# XRACER-IMU-R07.net
KiCad netlist of a schematic drawn in Altium Designer
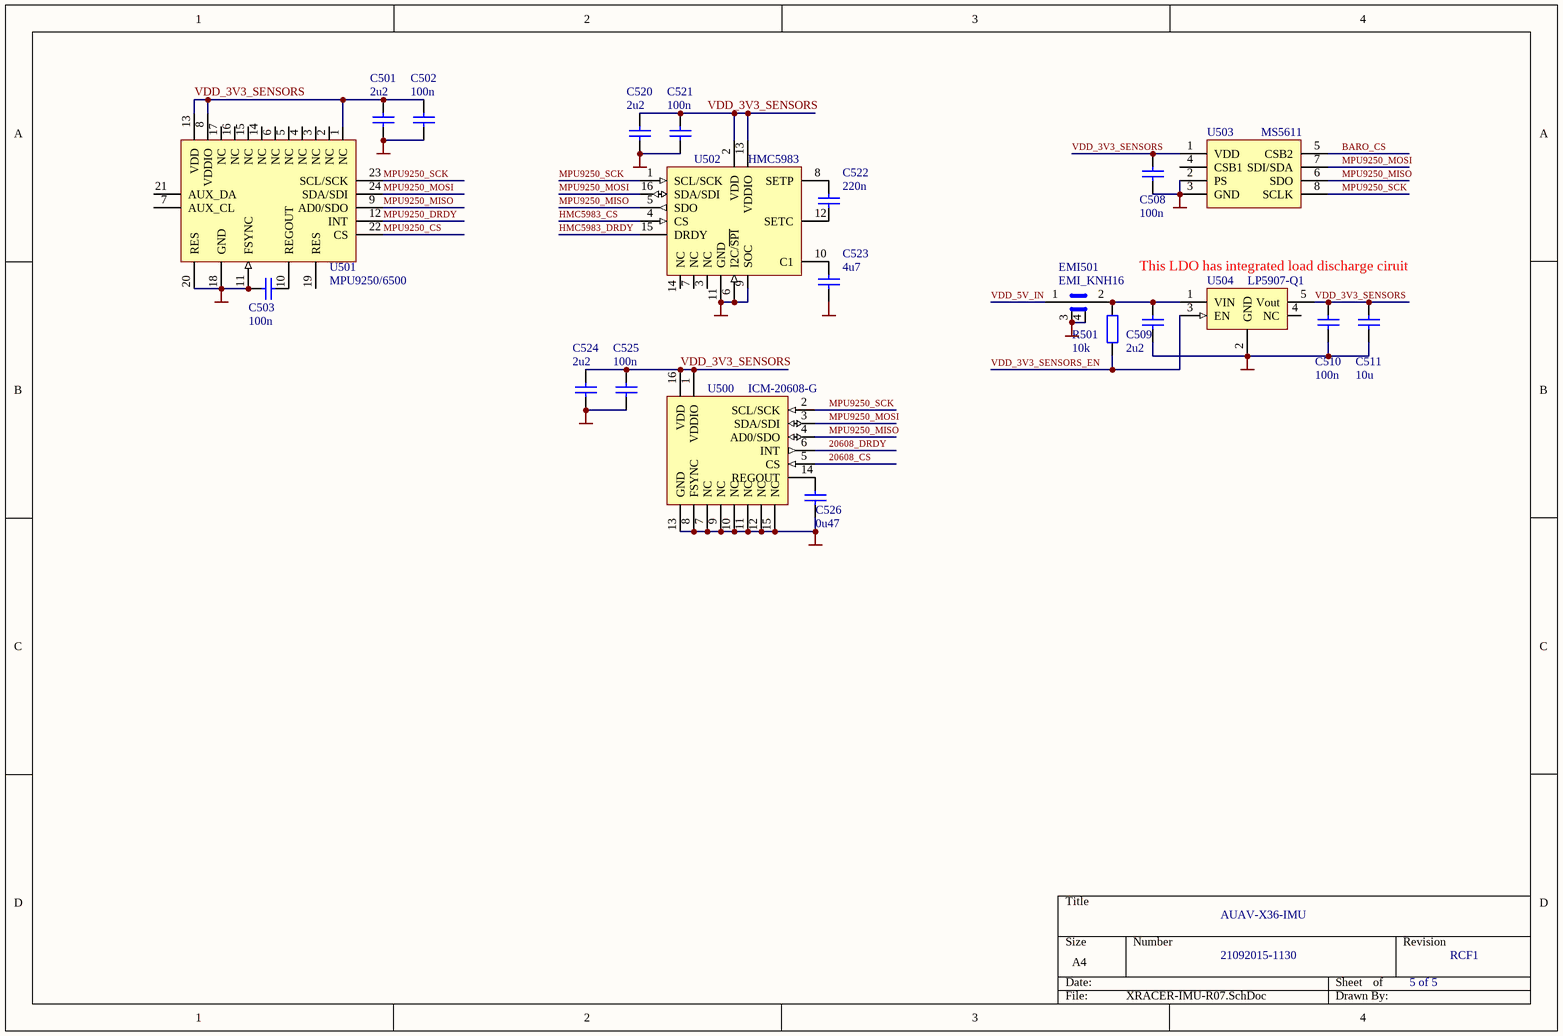
[diagram p0: XRACER-IMU-R07.SchDoc]

(export (version "E")
  (design (tool "Eeschema 10.0.6"))
  (components
    (comp (ref "C501")
      (value "2u2")
      (footprint "0402A")
      (description "Capacitor")
      (fields (field (name "PUBLISHER") "Altium Limited"))
      (libsource (lib "Miscellaneous Devices") (part "Cap"))
    )
    (comp (ref "C502")
      (value "100n")
      (footprint "0402A")
      (description "Capacitor")
      (fields (field (name "PUBLISHER") "Altium Limited"))
      (libsource (lib "Miscellaneous Devices") (part "Cap"))
    )
    (comp (ref "C503")
      (value "100n")
      (footprint "0402A")
      (description "Capacitor")
      (fields (field (name "PUBLISHER") "Altium Limited"))
      (libsource (lib "Miscellaneous Devices") (part "Cap"))
    )
    (comp (ref "C508")
      (value "100n")
      (footprint "0402A")
      (description "Capacitor")
      (fields (field (name "PUBLISHER") "Altium Limited"))
      (libsource (lib "Miscellaneous Devices") (part "Cap"))
    )
    (comp (ref "C509")
      (value "2u2")
      (footprint "0603A")
      (description "Capacitor")
      (fields (field (name "PUBLISHER") "Altium Limited"))
      (libsource (lib "Miscellaneous Devices") (part "Cap"))
    )
    (comp (ref "C510")
      (value "100n")
      (footprint "0603A")
      (description "Capacitor")
      (fields (field (name "PUBLISHER") "Altium Limited"))
      (libsource (lib "Miscellaneous Devices") (part "Cap"))
    )
    (comp (ref "C511")
      (value "10u")
      (footprint "0603A")
      (description "Capacitor")
      (fields (field (name "PUBLISHER") "Altium Limited"))
      (libsource (lib "Miscellaneous Devices") (part "Cap"))
    )
    (comp (ref "C520")
      (value "2u2")
      (footprint "0402A")
      (description "Capacitor")
      (fields (field (name "PUBLISHER") "Altium Limited"))
      (libsource (lib "Miscellaneous Devices") (part "Cap"))
    )
    (comp (ref "C521")
      (value "100n")
      (footprint "0402A")
      (description "Capacitor")
      (fields (field (name "PUBLISHER") "Altium Limited"))
      (libsource (lib "Miscellaneous Devices") (part "Cap"))
    )
    (comp (ref "C522")
      (value "220n")
      (footprint "0402A")
      (description "Capacitor")
      (fields (field (name "PUBLISHER") "Altium Limited"))
      (libsource (lib "Miscellaneous Devices") (part "Cap"))
    )
    (comp (ref "C523")
      (value "4u7")
      (footprint "0603A")
      (description "Capacitor")
      (fields (field (name "PUBLISHER") "Altium Limited"))
      (libsource (lib "Miscellaneous Devices") (part "Cap"))
    )
    (comp (ref "C524")
      (value "2u2")
      (footprint "0402A")
      (description "Capacitor")
      (fields (field (name "PUBLISHER") "Altium Limited"))
      (libsource (lib "Miscellaneous Devices") (part "Cap"))
    )
    (comp (ref "C525")
      (value "100n")
      (footprint "0402A")
      (description "Capacitor")
      (fields (field (name "PUBLISHER") "Altium Limited"))
      (libsource (lib "Miscellaneous Devices") (part "Cap"))
    )
    (comp (ref "C526")
      (value "0u47")
      (footprint "0402A")
      (description "Capacitor")
      (fields (field (name "PUBLISHER") "Altium Limited"))
      (libsource (lib "Miscellaneous Devices") (part "Cap"))
    )
    (comp (ref "EMI501")
      (value "EMI_KNH16")
      (footprint "EMI_KNH16_0603")
      (libsource (lib "My_Altium") (part "EMI_KNH16"))
    )
    (comp (ref "R501")
      (value "10k")
      (footprint "0603A")
      (description "Resistor")
      (fields (field (name "PUBLISHER") "Altium Limited"))
      (libsource (lib "Miscellaneous Devices") (part "Res2"))
    )
    (comp (ref "U500")
      (value "ICM-20608-G")
      (footprint "HCLGA-16L")
      (libsource (lib "My_Altium") (part "ICM-20608-G"))
    )
    (comp (ref "U501")
      (value "MPU9250/6500")
      (footprint "MPU6500-9250")
      (libsource (lib "My_Altium") (part "MPU6500"))
    )
    (comp (ref "U502")
      (value "HMC5983")
      (footprint "HMC5883L")
      (libsource (lib "My_Altium") (part "HMC5983"))
    )
    (comp (ref "U503")
      (value "MS5611")
      (footprint "MS5611")
      (libsource (lib "My_Altium") (part "MS5611-01BA03"))
    )
    (comp (ref "U504")
      (value "LP5907-Q1")
      (footprint "SOT23-5")
      (libsource (lib "My_Altium") (part "LP5907-Q1"))
    )
  )
  (nets
    (net (code "1") (name "/20608_CS") (class "Default")
      (node (ref "U500") (pin "5") (pinfunction "CS_5") (pintype "input"))
    )
    (net (code "2") (name "/20608_DRDY") (class "Default")
      (node (ref "U500") (pin "6") (pinfunction "INT_6") (pintype "output"))
    )
    (net (code "3") (name "/BARO_CS") (class "Default")
      (node (ref "U503") (pin "5") (pinfunction "CSB2_5") (pintype "passive"))
    )
    (net (code "4") (name "/HMC5983_CS") (class "Default")
      (node (ref "U502") (pin "4") (pinfunction "CS_4") (pintype "input"))
    )
    (net (code "5") (name "/HMC5983_DRDY") (class "Default")
      (node (ref "U502") (pin "15") (pinfunction "DRDY_15") (pintype "passive"))
    )
    (net (code "6") (name "/MPU9250_CS") (class "Default")
      (node (ref "U501") (pin "22") (pinfunction "CS_22") (pintype "passive"))
    )
    (net (code "7") (name "/MPU9250_DRDY") (class "Default")
      (node (ref "U501") (pin "12") (pinfunction "INT_12") (pintype "passive"))
    )
    (net (code "8") (name "/MPU9250_MISO") (class "Default")
      (node (ref "U500") (pin "4") (pinfunction "AD0/SDO_4") (pintype "bidirectional"))
      (node (ref "U501") (pin "9") (pinfunction "AD0/SDO_9") (pintype "passive"))
      (node (ref "U502") (pin "5") (pinfunction "SDO_5") (pintype "output"))
      (node (ref "U503") (pin "6") (pinfunction "SDO_6") (pintype "passive"))
    )
    (net (code "9") (name "/MPU9250_MOSI") (class "Default")
      (node (ref "U500") (pin "3") (pinfunction "SDA/SDI_3") (pintype "bidirectional"))
      (node (ref "U501") (pin "24") (pinfunction "SDA/SDI_24") (pintype "passive"))
      (node (ref "U502") (pin "16") (pinfunction "SDA/SDI_16") (pintype "bidirectional"))
      (node (ref "U503") (pin "7") (pinfunction "SDI/SDA_7") (pintype "passive"))
    )
    (net (code "10") (name "/MPU9250_SCK") (class "Default")
      (node (ref "U500") (pin "2") (pinfunction "SCL/SCK_2") (pintype "input"))
      (node (ref "U501") (pin "23") (pinfunction "SCL/SCK_23") (pintype "passive"))
      (node (ref "U502") (pin "1") (pinfunction "SCL/SCK_1") (pintype "input"))
      (node (ref "U503") (pin "8") (pinfunction "SCLK_8") (pintype "passive"))
    )
    (net (code "11") (name "/VDD_3V3_SENSORS") (class "Default")
      (node (ref "C501") (pin "2") (pinfunction "2_2") (pintype "passive"))
      (node (ref "C502") (pin "2") (pinfunction "2_2") (pintype "passive"))
      (node (ref "C508") (pin "2") (pinfunction "2_2") (pintype "passive"))
      (node (ref "C510") (pin "2") (pinfunction "2_2") (pintype "passive"))
      (node (ref "C511") (pin "2") (pinfunction "2_2") (pintype "passive"))
      (node (ref "C520") (pin "2") (pinfunction "2_2") (pintype "passive"))
      (node (ref "C521") (pin "2") (pinfunction "2_2") (pintype "passive"))
      (node (ref "C524") (pin "2") (pinfunction "2_2") (pintype "passive"))
      (node (ref "C525") (pin "2") (pinfunction "2_2") (pintype "passive"))
      (node (ref "U500") (pin "1") (pinfunction "VDDIO_1") (pintype "power_in"))
      (node (ref "U500") (pin "16") (pinfunction "VDD_16") (pintype "power_in"))
      (node (ref "U501") (pin "1") (pinfunction "NC_1") (pintype "passive"))
      (node (ref "U501") (pin "13") (pinfunction "VDD_13") (pintype "power_in"))
      (node (ref "U501") (pin "8") (pinfunction "VDDIO_8") (pintype "power_in"))
      (node (ref "U502") (pin "13") (pinfunction "VDDIO_13") (pintype "power_in"))
      (node (ref "U502") (pin "2") (pinfunction "VDD_2") (pintype "power_in"))
      (node (ref "U503") (pin "1") (pinfunction "VDD_1") (pintype "power_in"))
      (node (ref "U504") (pin "5") (pinfunction "Vout_5") (pintype "power_in"))
    )
    (net (code "12") (name "/VDD_3V3_SENSORS_EN") (class "Default")
      (node (ref "R501") (pin "1") (pinfunction "1_1") (pintype "passive"))
      (node (ref "U504") (pin "3") (pinfunction "EN_3") (pintype "input"))
    )
    (net (code "13") (name "/VDD_5V_IN") (class "Default")
      (node (ref "EMI501") (pin "1") (pinfunction "L1_1") (pintype "passive"))
    )
    (net (code "14") (name "GND") (class "Default")
      (node (ref "C501") (pin "1") (pinfunction "1_1") (pintype "passive"))
      (node (ref "C502") (pin "1") (pinfunction "1_1") (pintype "passive"))
      (node (ref "C503") (pin "1") (pinfunction "1_1") (pintype "passive"))
      (node (ref "C508") (pin "1") (pinfunction "1_1") (pintype "passive"))
      (node (ref "C509") (pin "1") (pinfunction "1_1") (pintype "passive"))
      (node (ref "C510") (pin "1") (pinfunction "1_1") (pintype "passive"))
      (node (ref "C511") (pin "1") (pinfunction "1_1") (pintype "passive"))
      (node (ref "C520") (pin "1") (pinfunction "1_1") (pintype "passive"))
      (node (ref "C521") (pin "1") (pinfunction "1_1") (pintype "passive"))
      (node (ref "C523") (pin "1") (pinfunction "1_1") (pintype "passive"))
      (node (ref "C524") (pin "1") (pinfunction "1_1") (pintype "passive"))
      (node (ref "C525") (pin "1") (pinfunction "1_1") (pintype "passive"))
      (node (ref "C526") (pin "1") (pinfunction "1_1") (pintype "passive"))
      (node (ref "EMI501") (pin "3") (pinfunction "G_3") (pintype "power_in"))
      (node (ref "EMI501") (pin "4") (pinfunction "G_4") (pintype "passive"))
      (node (ref "U500") (pin "10") (pinfunction "NC_10") (pintype "passive"))
      (node (ref "U500") (pin "11") (pinfunction "NC_11") (pintype "passive"))
      (node (ref "U500") (pin "12") (pinfunction "NC_12") (pintype "passive"))
      (node (ref "U500") (pin "13") (pinfunction "GND_13") (pintype "power_in"))
      (node (ref "U500") (pin "15") (pinfunction "NC_15") (pintype "passive"))
      (node (ref "U500") (pin "7") (pinfunction "NC_7") (pintype "passive"))
      (node (ref "U500") (pin "8") (pinfunction "FSYNC_8") (pintype "passive"))
      (node (ref "U500") (pin "9") (pinfunction "NC_9") (pintype "passive"))
      (node (ref "U501") (pin "11") (pinfunction "FSYNC_11") (pintype "input"))
      (node (ref "U501") (pin "18") (pinfunction "GND_18") (pintype "power_in"))
      (node (ref "U501") (pin "20") (pinfunction "RES_20") (pintype "passive"))
      (node (ref "U502") (pin "11") (pinfunction "GND_11") (pintype "power_in"))
      (node (ref "U502") (pin "6") (pinfunction "I2C/~{SPI}_6") (pintype "input"))
      (node (ref "U502") (pin "9") (pinfunction "SOC_9") (pintype "power_in"))
      (node (ref "U503") (pin "2") (pinfunction "PS_2") (pintype "passive"))
      (node (ref "U503") (pin "3") (pinfunction "GND_3") (pintype "power_in"))
      (node (ref "U504") (pin "2") (pinfunction "GND_2") (pintype "power_in"))
    )
    (net (code "15") (name "Net-(EMI501-L2)") (class "Default")
      (node (ref "C509") (pin "2") (pinfunction "2_2") (pintype "passive"))
      (node (ref "EMI501") (pin "2") (pinfunction "L2_2") (pintype "passive"))
      (node (ref "R501") (pin "2") (pinfunction "2_2") (pintype "passive"))
      (node (ref "U504") (pin "1") (pinfunction "VIN_1") (pintype "power_in"))
    )
    (net (code "16") (name "Net-(U500-REGOUT)") (class "Default")
      (node (ref "C526") (pin "2") (pinfunction "2_2") (pintype "passive"))
      (node (ref "U500") (pin "14") (pinfunction "REGOUT_14") (pintype "passive"))
    )
    (net (code "17") (name "Net-(U501-REGOUT)") (class "Default")
      (node (ref "C503") (pin "2") (pinfunction "2_2") (pintype "passive"))
      (node (ref "U501") (pin "10") (pinfunction "REGOUT_10") (pintype "passive"))
    )
    (net (code "18") (name "Net-(U502-C1)") (class "Default")
      (node (ref "C523") (pin "2") (pinfunction "2_2") (pintype "passive"))
      (node (ref "U502") (pin "10") (pinfunction "C1_10") (pintype "passive"))
    )
    (net (code "19") (name "Net-(U502-SETC)") (class "Default")
      (node (ref "C522") (pin "1") (pinfunction "1_1") (pintype "passive"))
      (node (ref "U502") (pin "12") (pinfunction "SETC_12") (pintype "passive"))
    )
    (net (code "20") (name "Net-(U502-SETP)") (class "Default")
      (node (ref "C522") (pin "2") (pinfunction "2_2") (pintype "passive"))
      (node (ref "U502") (pin "8") (pinfunction "SETP_8") (pintype "passive"))
    )
    (net (code "21") (name "unconnected-(U501-AUX_CL-Pad7)") (class "Default")
      (node (ref "U501") (pin "7") (pinfunction "AUX_CL_7") (pintype "passive"))
    )
    (net (code "22") (name "unconnected-(U501-AUX_DA-Pad21)") (class "Default")
      (node (ref "U501") (pin "21") (pinfunction "AUX_DA_21") (pintype "passive"))
    )
    (net (code "23") (name "unconnected-(U501-NC-Pad2)") (class "Default")
      (node (ref "U501") (pin "2") (pinfunction "NC_2") (pintype "passive"))
    )
    (net (code "24") (name "unconnected-(U501-NC-Pad3)") (class "Default")
      (node (ref "U501") (pin "3") (pinfunction "NC_3") (pintype "passive"))
    )
    (net (code "25") (name "unconnected-(U501-NC-Pad4)") (class "Default")
      (node (ref "U501") (pin "4") (pinfunction "NC_4") (pintype "passive"))
    )
    (net (code "26") (name "unconnected-(U501-NC-Pad5)") (class "Default")
      (node (ref "U501") (pin "5") (pinfunction "NC_5") (pintype "passive"))
    )
    (net (code "27") (name "unconnected-(U501-NC-Pad6)") (class "Default")
      (node (ref "U501") (pin "6") (pinfunction "NC_6") (pintype "passive"))
    )
    (net (code "28") (name "unconnected-(U501-NC-Pad14)") (class "Default")
      (node (ref "U501") (pin "14") (pinfunction "NC_14") (pintype "passive"))
    )
    (net (code "29") (name "unconnected-(U501-NC-Pad15)") (class "Default")
      (node (ref "U501") (pin "15") (pinfunction "NC_15") (pintype "passive"))
    )
    (net (code "30") (name "unconnected-(U501-NC-Pad16)") (class "Default")
      (node (ref "U501") (pin "16") (pinfunction "NC_16") (pintype "passive"))
    )
    (net (code "31") (name "unconnected-(U501-NC-Pad17)") (class "Default")
      (node (ref "U501") (pin "17") (pinfunction "NC_17") (pintype "passive"))
    )
    (net (code "32") (name "unconnected-(U501-RES-Pad19)") (class "Default")
      (node (ref "U501") (pin "19") (pinfunction "RES_19") (pintype "passive"))
    )
    (net (code "33") (name "unconnected-(U502-NC-Pad3)") (class "Default")
      (node (ref "U502") (pin "3") (pinfunction "NC_3") (pintype "passive"))
    )
    (net (code "34") (name "unconnected-(U502-NC-Pad7)") (class "Default")
      (node (ref "U502") (pin "7") (pinfunction "NC_7") (pintype "passive"))
    )
    (net (code "35") (name "unconnected-(U502-NC-Pad14)") (class "Default")
      (node (ref "U502") (pin "14") (pinfunction "NC_14") (pintype "passive"))
    )
    (net (code "36") (name "unconnected-(U503-CSB1-Pad4)") (class "Default")
      (node (ref "U503") (pin "4") (pinfunction "CSB1_4") (pintype "passive"))
    )
    (net (code "37") (name "unconnected-(U504-NC-Pad4)") (class "Default")
      (node (ref "U504") (pin "4") (pinfunction "NC_4") (pintype "passive"))
    )
  )
)
